# alimentador.net
KiCad netlist of a schematic drawn in EAGLE
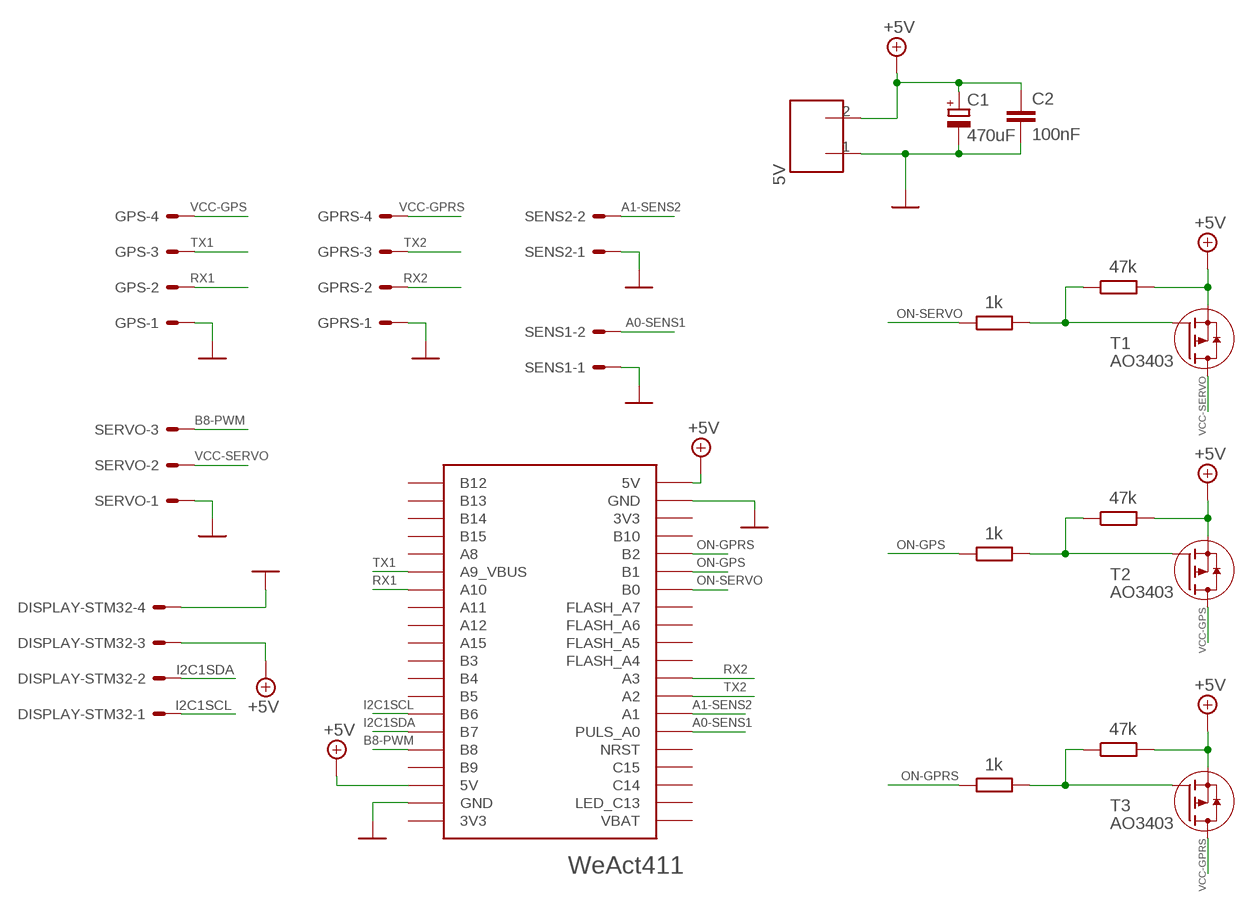
[diagram p0: schematic, sheet 1]

(export (version "E")
  (design (tool "Eeschema 10.0.6"))
  (components
    (comp (ref "5V")
      (value "CONECTOR_2P-3.81")
      (footprint "eagle-import:CON2P-3.81")
      (libsource (lib "eagle-import") (part "CONECTOR_2P-3.81"))
    )
    (comp (ref "C1")
      (value "470uF")
      (footprint "eagle-import:E5-10,5")
      (libsource (lib "eagle-import") (part "CPOL-EUE5-10.5"))
    )
    (comp (ref "C2")
      (value "100nF")
      (footprint "eagle-import:C1206")
      (libsource (lib "eagle-import") (part "C-EUC1206"))
    )
    (comp (ref "DISPLAY-STM32")
      (value "22-05-7048-04")
      (footprint "eagle-import:7395-04")
      (libsource (lib "eagle-import") (part "22-?-0405-7048"))
    )
    (comp (ref "GPRS")
      (value "22-27-2041-04")
      (footprint "eagle-import:6410-04")
      (libsource (lib "eagle-import") (part "22-?-0427-2041"))
    )
    (comp (ref "GPS")
      (value "22-27-2041-04")
      (footprint "eagle-import:6410-04")
      (libsource (lib "eagle-import") (part "22-?-0427-2041"))
    )
    (comp (ref "R1")
      (value "47k")
      (footprint "eagle-import:R1206")
      (libsource (lib "eagle-import") (part "R-EU_R1206"))
    )
    (comp (ref "R2")
      (value "47k")
      (footprint "eagle-import:R1206")
      (libsource (lib "eagle-import") (part "R-EU_R1206"))
    )
    (comp (ref "R3")
      (value "1k")
      (footprint "eagle-import:R1206")
      (libsource (lib "eagle-import") (part "R-EU_R1206"))
    )
    (comp (ref "R4")
      (value "1k")
      (footprint "eagle-import:R1206")
      (libsource (lib "eagle-import") (part "R-EU_R1206"))
    )
    (comp (ref "R5")
      (value "47k")
      (footprint "eagle-import:R1206")
      (libsource (lib "eagle-import") (part "R-EU_R1206"))
    )
    (comp (ref "R6")
      (value "1k")
      (footprint "eagle-import:R1206")
      (libsource (lib "eagle-import") (part "R-EU_R1206"))
    )
    (comp (ref "SENS1")
      (value "22-27-2021-02")
      (footprint "eagle-import:6410-02")
      (libsource (lib "eagle-import") (part "22-?-0227-2021"))
    )
    (comp (ref "SENS2")
      (value "22-27-2021-02")
      (footprint "eagle-import:6410-02")
      (libsource (lib "eagle-import") (part "22-?-0227-2021"))
    )
    (comp (ref "SERVO")
      (value "22-27-2031-03")
      (footprint "eagle-import:6410-03")
      (libsource (lib "eagle-import") (part "22-?-0327-2031"))
    )
    (comp (ref "T1")
      (value "AO3403")
      (footprint "eagle-import:SOT23")
      (libsource (lib "eagle-import") (part "AO3403"))
    )
    (comp (ref "T2")
      (value "AO3403")
      (footprint "eagle-import:SOT23")
      (libsource (lib "eagle-import") (part "AO3403"))
    )
    (comp (ref "T3")
      (value "AO3403")
      (footprint "eagle-import:SOT23")
      (libsource (lib "eagle-import") (part "AO3403"))
    )
    (comp (ref "U$2")
      (value "WEACT411")
      (footprint "eagle-import:WEACT411")
      (libsource (lib "eagle-import") (part "WEACT411"))
    )
  )
  (nets
    (net (code "1") (name "+5V") (class "Default")
      (node (ref "5V") (pin "2") (pinfunction "2_2") (pintype "bidirectional"))
      (node (ref "C1") (pin "+") (pinfunction "+_+") (pintype "passive"))
      (node (ref "C2") (pin "1") (pinfunction "1_1") (pintype "passive"))
      (node (ref "DISPLAY-STM32") (pin "3") (pinfunction "S_3") (pintype "passive"))
      (node (ref "U$2") (pin "5V@1") (pinfunction "5V_5V@1") (pintype "power_in"))
      (node (ref "U$2") (pin "5V@2") (pinfunction "5V_5V@2") (pintype "power_in"))
    )
    (net (code "2") (name "/A0-SENS1") (class "Default")
      (node (ref "SENS1") (pin "2") (pinfunction "S_2") (pintype "passive"))
      (node (ref "U$2") (pin "A0") (pinfunction "PULS_A0_A0") (pintype "bidirectional"))
    )
    (net (code "3") (name "/A1-SENS2") (class "Default")
      (node (ref "SENS2") (pin "2") (pinfunction "S_2") (pintype "passive"))
      (node (ref "U$2") (pin "A1") (pinfunction "A1_A1") (pintype "bidirectional"))
    )
    (net (code "4") (name "/B8-PWM") (class "Default")
      (node (ref "SERVO") (pin "3") (pinfunction "S_3") (pintype "passive"))
      (node (ref "U$2") (pin "B8") (pinfunction "B8_B8") (pintype "bidirectional"))
    )
    (net (code "5") (name "/I2C1SCL") (class "Default")
      (node (ref "DISPLAY-STM32") (pin "1") (pinfunction "S_1") (pintype "passive"))
      (node (ref "U$2") (pin "B6") (pinfunction "B6_B6") (pintype "bidirectional"))
    )
    (net (code "6") (name "/I2C1SDA") (class "Default")
      (node (ref "DISPLAY-STM32") (pin "2") (pinfunction "S_2") (pintype "passive"))
      (node (ref "U$2") (pin "B7") (pinfunction "B7_B7") (pintype "bidirectional"))
    )
    (net (code "7") (name "/ON-GPRS") (class "Default")
      (node (ref "R6") (pin "1") (pinfunction "1_1") (pintype "passive"))
      (node (ref "U$2") (pin "B2") (pinfunction "B2_B2") (pintype "bidirectional"))
    )
    (net (code "8") (name "/ON-GPS") (class "Default")
      (node (ref "R4") (pin "1") (pinfunction "1_1") (pintype "passive"))
      (node (ref "U$2") (pin "B1") (pinfunction "B1_B1") (pintype "bidirectional"))
    )
    (net (code "9") (name "/ON-SERVO") (class "Default")
      (node (ref "R3") (pin "1") (pinfunction "1_1") (pintype "passive"))
      (node (ref "U$2") (pin "B0") (pinfunction "B0_B0") (pintype "bidirectional"))
    )
    (net (code "10") (name "/RX1") (class "Default")
      (node (ref "GPS") (pin "2") (pinfunction "S_2") (pintype "passive"))
      (node (ref "U$2") (pin "A10") (pinfunction "A10_A10") (pintype "bidirectional"))
    )
    (net (code "11") (name "/RX2") (class "Default")
      (node (ref "GPRS") (pin "2") (pinfunction "S_2") (pintype "passive"))
      (node (ref "U$2") (pin "A3") (pinfunction "A3_A3") (pintype "bidirectional"))
    )
    (net (code "12") (name "/TX1") (class "Default")
      (node (ref "GPS") (pin "3") (pinfunction "S_3") (pintype "passive"))
      (node (ref "U$2") (pin "A9") (pinfunction "A9_VBUS_A9") (pintype "bidirectional"))
    )
    (net (code "13") (name "/TX2") (class "Default")
      (node (ref "GPRS") (pin "3") (pinfunction "S_3") (pintype "passive"))
      (node (ref "U$2") (pin "A2") (pinfunction "A2_A2") (pintype "bidirectional"))
    )
    (net (code "14") (name "/VBAT") (class "Default")
      (node (ref "U$2") (pin "VBAT") (pinfunction "VBAT_VBAT") (pintype "power_in"))
    )
    (net (code "15") (name "/VCC-GPRS") (class "Default")
      (node (ref "GPRS") (pin "4") (pinfunction "S_4") (pintype "passive"))
      (node (ref "T3") (pin "3") (pinfunction "D_3") (pintype "passive"))
    )
    (net (code "16") (name "/VCC-GPS") (class "Default")
      (node (ref "GPS") (pin "4") (pinfunction "S_4") (pintype "passive"))
      (node (ref "T2") (pin "3") (pinfunction "D_3") (pintype "passive"))
    )
    (net (code "17") (name "/VCC-SERVO") (class "Default")
      (node (ref "SERVO") (pin "2") (pinfunction "S_2") (pintype "passive"))
      (node (ref "T1") (pin "3") (pinfunction "D_3") (pintype "passive"))
    )
    (net (code "18") (name "GND") (class "Default")
      (node (ref "5V") (pin "1") (pinfunction "1_1") (pintype "bidirectional"))
      (node (ref "C1") (pin "-") (pinfunction "-_-") (pintype "passive"))
      (node (ref "C2") (pin "2") (pinfunction "2_2") (pintype "passive"))
      (node (ref "DISPLAY-STM32") (pin "4") (pinfunction "S_4") (pintype "passive"))
      (node (ref "GPRS") (pin "1") (pinfunction "S_1") (pintype "passive"))
      (node (ref "GPS") (pin "1") (pinfunction "S_1") (pintype "passive"))
      (node (ref "SENS1") (pin "1") (pinfunction "S_1") (pintype "passive"))
      (node (ref "SENS2") (pin "1") (pinfunction "S_1") (pintype "passive"))
      (node (ref "SERVO") (pin "1") (pinfunction "S_1") (pintype "passive"))
      (node (ref "U$2") (pin "GND@1") (pinfunction "GND_GND@1") (pintype "power_in"))
      (node (ref "U$2") (pin "GND@2") (pinfunction "GND_GND@2") (pintype "power_in"))
    )
    (net (code "19") (name "Net-(T1-G)") (class "Default")
      (node (ref "R2") (pin "1") (pinfunction "1_1") (pintype "passive"))
      (node (ref "R3") (pin "2") (pinfunction "2_2") (pintype "passive"))
      (node (ref "T1") (pin "1") (pinfunction "G_1") (pintype "passive"))
    )
    (net (code "20") (name "Net-(T1-S)") (class "Default")
      (node (ref "R2") (pin "2") (pinfunction "2_2") (pintype "passive"))
      (node (ref "T1") (pin "2") (pinfunction "S_2") (pintype "passive"))
    )
    (net (code "21") (name "Net-(T2-G)") (class "Default")
      (node (ref "R1") (pin "1") (pinfunction "1_1") (pintype "passive"))
      (node (ref "R4") (pin "2") (pinfunction "2_2") (pintype "passive"))
      (node (ref "T2") (pin "1") (pinfunction "G_1") (pintype "passive"))
    )
    (net (code "22") (name "Net-(T2-S)") (class "Default")
      (node (ref "R1") (pin "2") (pinfunction "2_2") (pintype "passive"))
      (node (ref "T2") (pin "2") (pinfunction "S_2") (pintype "passive"))
    )
    (net (code "23") (name "Net-(T3-G)") (class "Default")
      (node (ref "R5") (pin "1") (pinfunction "1_1") (pintype "passive"))
      (node (ref "R6") (pin "2") (pinfunction "2_2") (pintype "passive"))
      (node (ref "T3") (pin "1") (pinfunction "G_1") (pintype "passive"))
    )
    (net (code "24") (name "Net-(T3-S)") (class "Default")
      (node (ref "R5") (pin "2") (pinfunction "2_2") (pintype "passive"))
      (node (ref "T3") (pin "2") (pinfunction "S_2") (pintype "passive"))
    )
    (net (code "25") (name "unconnected-(U$2-3V3-Pad3V3@1)") (class "Default")
      (node (ref "U$2") (pin "3V3@1") (pinfunction "3V3_3V3@1") (pintype "bidirectional"))
    )
    (net (code "26") (name "unconnected-(U$2-3V3-Pad3V3@2)") (class "Default")
      (node (ref "U$2") (pin "3V3@2") (pinfunction "3V3_3V3@2") (pintype "bidirectional"))
    )
    (net (code "27") (name "unconnected-(U$2-FLASH_A4-PadA4)") (class "Default")
      (node (ref "U$2") (pin "A4") (pinfunction "FLASH_A4_A4") (pintype "bidirectional"))
    )
    (net (code "28") (name "unconnected-(U$2-FLASH_A5-PadA5)") (class "Default")
      (node (ref "U$2") (pin "A5") (pinfunction "FLASH_A5_A5") (pintype "bidirectional"))
    )
    (net (code "29") (name "unconnected-(U$2-FLASH_A6-PadA6)") (class "Default")
      (node (ref "U$2") (pin "A6") (pinfunction "FLASH_A6_A6") (pintype "bidirectional"))
    )
    (net (code "30") (name "unconnected-(U$2-FLASH_A7-PadA7)") (class "Default")
      (node (ref "U$2") (pin "A7") (pinfunction "FLASH_A7_A7") (pintype "bidirectional"))
    )
    (net (code "31") (name "unconnected-(U$2-LED_C13-PadC13)") (class "Default")
      (node (ref "U$2") (pin "C13") (pinfunction "LED_C13_C13") (pintype "bidirectional"))
    )
    (net (code "32") (name "unconnected-(U$2-PadA8)") (class "Default")
      (node (ref "U$2") (pin "A8") (pinfunction "A8_A8") (pintype "bidirectional"))
    )
    (net (code "33") (name "unconnected-(U$2-PadA11)") (class "Default")
      (node (ref "U$2") (pin "A11") (pinfunction "A11_A11") (pintype "bidirectional"))
    )
    (net (code "34") (name "unconnected-(U$2-PadA12)") (class "Default")
      (node (ref "U$2") (pin "A12") (pinfunction "A12_A12") (pintype "bidirectional"))
    )
    (net (code "35") (name "unconnected-(U$2-PadA15)") (class "Default")
      (node (ref "U$2") (pin "A15") (pinfunction "A15_A15") (pintype "bidirectional"))
    )
    (net (code "36") (name "unconnected-(U$2-PadB3)") (class "Default")
      (node (ref "U$2") (pin "B3") (pinfunction "B3_B3") (pintype "bidirectional"))
    )
    (net (code "37") (name "unconnected-(U$2-PadB4)") (class "Default")
      (node (ref "U$2") (pin "B4") (pinfunction "B4_B4") (pintype "bidirectional"))
    )
    (net (code "38") (name "unconnected-(U$2-PadB5)") (class "Default")
      (node (ref "U$2") (pin "B5") (pinfunction "B5_B5") (pintype "bidirectional"))
    )
    (net (code "39") (name "unconnected-(U$2-PadB9)") (class "Default")
      (node (ref "U$2") (pin "B9") (pinfunction "B9_B9") (pintype "bidirectional"))
    )
    (net (code "40") (name "unconnected-(U$2-PadB10)") (class "Default")
      (node (ref "U$2") (pin "B10") (pinfunction "B10_B10") (pintype "bidirectional"))
    )
    (net (code "41") (name "unconnected-(U$2-PadB12)") (class "Default")
      (node (ref "U$2") (pin "B12") (pinfunction "B12_B12") (pintype "bidirectional"))
    )
    (net (code "42") (name "unconnected-(U$2-PadB13)") (class "Default")
      (node (ref "U$2") (pin "B13") (pinfunction "B13_B13") (pintype "bidirectional"))
    )
    (net (code "43") (name "unconnected-(U$2-PadB14)") (class "Default")
      (node (ref "U$2") (pin "B14") (pinfunction "B14_B14") (pintype "bidirectional"))
    )
    (net (code "44") (name "unconnected-(U$2-PadB15)") (class "Default")
      (node (ref "U$2") (pin "B15") (pinfunction "B15_B15") (pintype "bidirectional"))
    )
    (net (code "45") (name "unconnected-(U$2-PadC14)") (class "Default")
      (node (ref "U$2") (pin "C14") (pinfunction "C14_C14") (pintype "bidirectional"))
    )
    (net (code "46") (name "unconnected-(U$2-PadC15)") (class "Default")
      (node (ref "U$2") (pin "C15") (pinfunction "C15_C15") (pintype "bidirectional"))
    )
    (net (code "47") (name "unconnected-(U$2-PadNRST)") (class "Default")
      (node (ref "U$2") (pin "NRST") (pinfunction "NRST_NRST") (pintype "bidirectional"))
    )
  )
)
